# Sheet1.net
KiCad netlist of a schematic drawn in Altium Designer
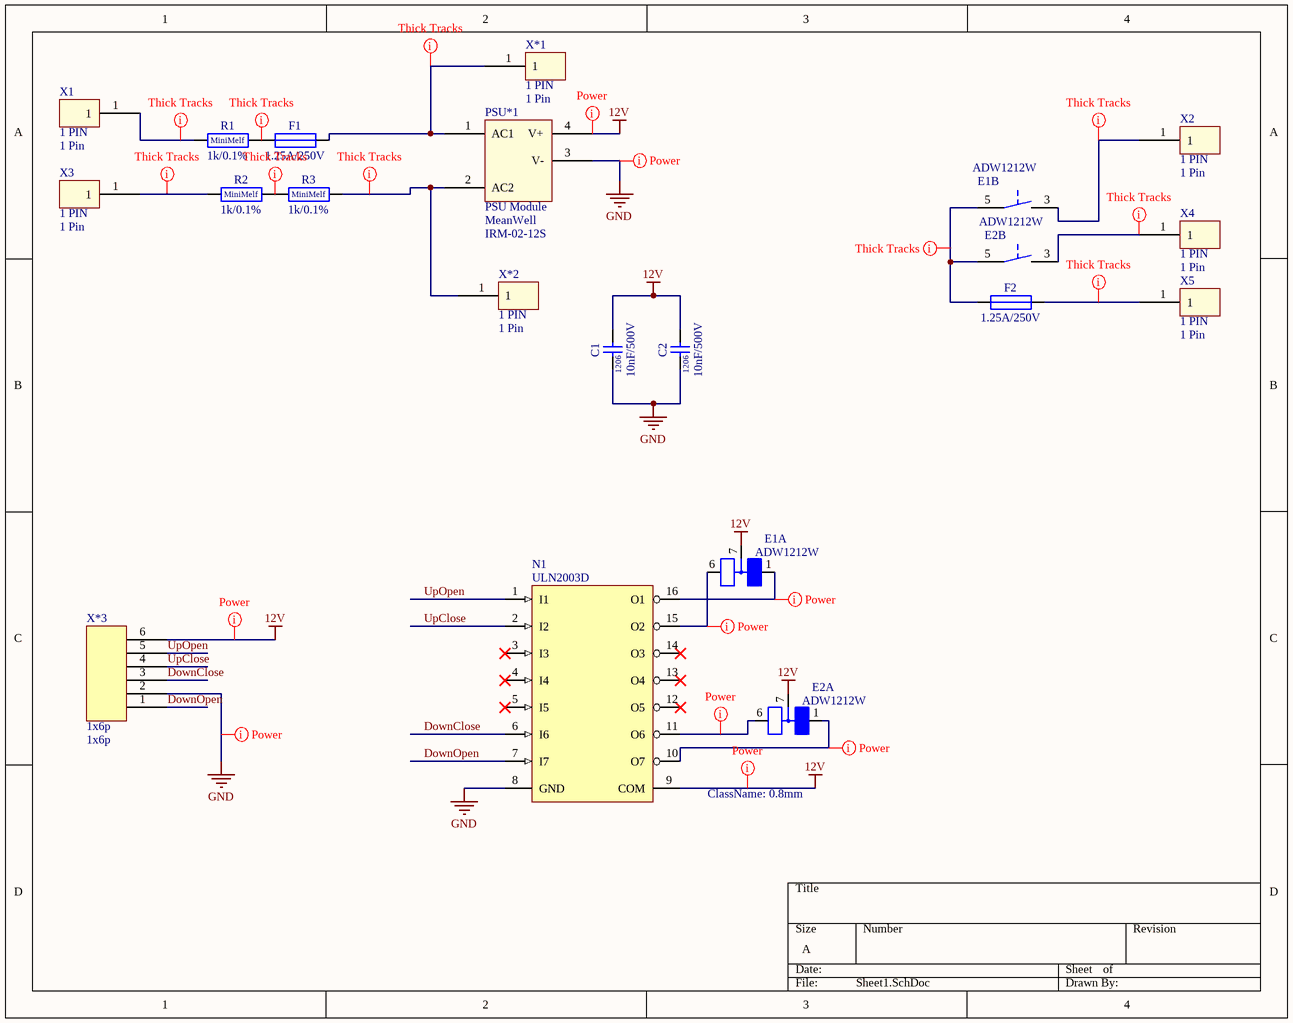
[diagram p0: Sheet1.SchDoc]

(export (version "E")
  (design (tool "Eeschema 10.0.6"))
  (components
    (comp (ref "C1")
      (value "10nF/500V")
      (footprint "CAP_1206_IPC_B")
      (description "02-1257 - SMD Capacitor 1206 10nF 500V X7R")
      (fields (field (name "PARTNUMBER") "02-1257") (field (name "PUBLISHER") "SS"))
      (libsource (lib "02_KONDENSATOREN") (part "10nF_500V_1206_02-1257"))
    )
    (comp (ref "C2")
      (value "10nF/500V")
      (footprint "CAP_1206_IPC_B")
      (description "02-1257 - SMD Capacitor 1206 10nF 500V X7R")
      (fields (field (name "PARTNUMBER") "02-1257") (field (name "PUBLISHER") "SS"))
      (libsource (lib "02_KONDENSATOREN") (part "10nF_500V_1206_02-1257"))
    )
    (comp (ref "E1")
      (value "ADW1212W")
      (footprint "RELAIS_PANASONIC_ADW1212W")
      (description "04-3960 - Relais, 12V, 1S 2Coils")
      (fields (field (name "PARTNUMBER") "04-3960") (field (name "PUBLISHER") "SS"))
      (libsource (lib "") (part "ADW1212W_04-3960_2"))
    )
    (comp (ref "E2")
      (value "ADW1212W")
      (footprint "RELAIS_PANASONIC_ADW1212W")
      (description "04-3960 - Relais, 12V, 1S 2Coils")
      (fields (field (name "PARTNUMBER") "04-3960") (field (name "PUBLISHER") "SS"))
      (libsource (lib "") (part "ADW1212W_04-3960_1"))
    )
    (comp (ref "F1")
      (value "1.25A/250V")
      (footprint "Fuse")
      (description "04-3586 - Fuse 1.25A 250V THT 8.4x4mm RM5.08mm")
      (fields (field (name "PARTNUMBER") "04-3586") (field (name "PUBLISHER") "SS"))
      (libsource (lib "AM540_rf1_1v4") (part "Fuse_1.25A_250V_04-3586"))
    )
    (comp (ref "F2")
      (value "1.25A/250V")
      (footprint "Fuse")
      (description "04-3586 - Fuse 1.25A 250V THT 8.4x4mm RM5.08mm")
      (fields (field (name "PARTNUMBER") "04-3586") (field (name "PUBLISHER") "SS"))
      (libsource (lib "AM540_rf1_1v4") (part "Fuse_1.25A_250V_04-3586"))
    )
    (comp (ref "N1")
      (value "ULN2003D")
      (footprint "SOP127P720X175-16N")
      (description "11-0373- High-Voltage, High-Current Darlington Transistor Arrays, SOP16")
      (fields (field (name "PARTNUMBER") "11-0373") (field (name "PUBLISHER") "SS"))
      (libsource (lib "Mainboard_abc082rn1_Rev18") (part "ULN2003D_11-0373"))
    )
    (comp (ref "PSU*1")
      (value "PSU Module")
      (footprint "RAC02-GB")
      (description "SMPS PCB Mode")
      (fields (field (name "MANUFACTURER") "MeanWell") (field (name "MANUFACTURER CODE") "IRM-02-12S"))
      (libsource (lib "Blinds") (part "PSU Module"))
    )
    (comp (ref "R1")
      (value "1k/0.1%")
      (footprint "RES_MiniMELF_3514N")
      (description "01-3006 - SMD Resistor MiniMelf 0.25W 0.1%")
      (fields
        (field (name "PARTNUMBER") "01-3006")
        (field (name "HELPURL") "N:\\data\\Solutions\\etw\\Projekte\\Bibliotheken\\Bauteil-Neuanlagen\\Datenblätter\\01er-Parts\\")
        (field (name "PUBLISHER") "DD")
      )
      (libsource (lib "01_WIDERSTAENDE") (part "1k_MiniMelf_01-3006"))
    )
    (comp (ref "R2")
      (value "1k/0.1%")
      (footprint "RES_MiniMELF_3514N")
      (description "01-3006 - SMD Resistor MiniMelf 0.25W 0.1%")
      (fields
        (field (name "PARTNUMBER") "01-3006")
        (field (name "HELPURL") "N:\\data\\Solutions\\etw\\Projekte\\Bibliotheken\\Bauteil-Neuanlagen\\Datenblätter\\01er-Parts\\")
        (field (name "PUBLISHER") "DD")
      )
      (libsource (lib "01_WIDERSTAENDE") (part "1k_MiniMelf_01-3006"))
    )
    (comp (ref "R3")
      (value "1k/0.1%")
      (footprint "RES_MiniMELF_3514N")
      (description "01-3006 - SMD Resistor MiniMelf 0.25W 0.1%")
      (fields
        (field (name "PARTNUMBER") "01-3006")
        (field (name "HELPURL") "N:\\data\\Solutions\\etw\\Projekte\\Bibliotheken\\Bauteil-Neuanlagen\\Datenblätter\\01er-Parts\\")
        (field (name "PUBLISHER") "DD")
      )
      (libsource (lib "01_WIDERSTAENDE") (part "1k_MiniMelf_01-3006"))
    )
    (comp (ref "X*1")
      (value "1 PIN")
      (footprint "1p")
      (fields (field (name "1") "1 Pin"))
      (libsource (lib "Blinds") (part "1 PIN"))
    )
    (comp (ref "X*2")
      (value "1 PIN")
      (footprint "1p")
      (fields (field (name "1") "1 Pin"))
      (libsource (lib "Blinds") (part "1 PIN"))
    )
    (comp (ref "X*3")
      (value "1x6p")
      (footprint "M22-5330605")
      (fields (field (name "MANUFACTURER") "TI") (field (name "MANUFACTURER CODE") "1x6p"))
      (libsource (lib "Blinds") (part "1x6p"))
    )
    (comp (ref "X1")
      (value "1 PIN")
      (footprint "1p")
      (fields (field (name "1") "1 Pin"))
      (libsource (lib "") (part "1 PIN_1"))
    )
    (comp (ref "X2")
      (value "1 PIN")
      (footprint "1p")
      (fields (field (name "1") "1 Pin"))
      (libsource (lib "Blinds") (part "1 PIN"))
    )
    (comp (ref "X3")
      (value "1 PIN")
      (footprint "1p")
      (fields (field (name "1") "1 Pin"))
      (libsource (lib "") (part "1 PIN_1"))
    )
    (comp (ref "X4")
      (value "1 PIN")
      (footprint "1p")
      (fields (field (name "1") "1 Pin"))
      (libsource (lib "Blinds") (part "1 PIN"))
    )
    (comp (ref "X5")
      (value "1 PIN")
      (footprint "1p")
      (fields (field (name "1") "1 Pin"))
      (libsource (lib "Blinds") (part "1 PIN"))
    )
  )
  (nets
    (net (code "1") (name "/DownClose") (class "Default")
      (node (ref "N1") (pin "6") (pinfunction "I6_6") (pintype "input"))
      (node (ref "X*3") (pin "3") (pintype "passive"))
    )
    (net (code "2") (name "/DownOpen") (class "Default")
      (node (ref "N1") (pin "7") (pinfunction "I7_7") (pintype "input"))
      (node (ref "X*3") (pin "1") (pintype "passive"))
    )
    (net (code "3") (name "/UpClose") (class "Default")
      (node (ref "N1") (pin "2") (pinfunction "I2_2") (pintype "input"))
      (node (ref "X*3") (pin "4") (pintype "passive"))
    )
    (net (code "4") (name "/UpOpen") (class "Default")
      (node (ref "N1") (pin "1") (pinfunction "I1_1") (pintype "input"))
      (node (ref "X*3") (pin "5") (pintype "passive"))
    )
    (net (code "5") (name "12V") (class "Default")
      (node (ref "C1") (pin "2") (pinfunction "2_2") (pintype "passive"))
      (node (ref "C2") (pin "2") (pinfunction "2_2") (pintype "passive"))
      (node (ref "E1") (pin "7") (pinfunction "P_7") (pintype "passive"))
      (node (ref "E2") (pin "7") (pinfunction "P_7") (pintype "passive"))
      (node (ref "N1") (pin "9") (pinfunction "COM_9") (pintype "passive"))
      (node (ref "PSU*1") (pin "4") (pinfunction "V+_4") (pintype "passive"))
      (node (ref "X*3") (pin "6") (pintype "passive"))
    )
    (net (code "6") (name "GND") (class "Default")
      (node (ref "C1") (pin "1") (pinfunction "1_1") (pintype "passive"))
      (node (ref "C2") (pin "1") (pinfunction "1_1") (pintype "passive"))
      (node (ref "N1") (pin "8") (pinfunction "GND_8") (pintype "power_in"))
      (node (ref "PSU*1") (pin "3") (pinfunction "V-_3") (pintype "passive"))
      (node (ref "X*3") (pin "2") (pintype "passive"))
    )
    (net (code "7") (name "Net-(E1-Pad3)") (class "Default")
      (node (ref "E1") (pin "3") (pinfunction "3_3") (pintype "passive"))
      (node (ref "X2") (pin "1") (pinfunction "1_1") (pintype "passive"))
    )
    (net (code "8") (name "Net-(E1-Pad5)") (class "Default")
      (node (ref "E1") (pin "5") (pinfunction "5_5") (pintype "passive"))
      (node (ref "E2") (pin "5") (pinfunction "5_5") (pintype "passive"))
      (node (ref "F2") (pin "1") (pinfunction "1_1") (pintype "passive"))
    )
    (net (code "9") (name "Net-(E1A-M)") (class "Default")
      (node (ref "E1") (pin "1") (pinfunction "M_1") (pintype "passive"))
      (node (ref "N1") (pin "16") (pinfunction "O1_16") (pintype "passive"))
    )
    (net (code "10") (name "Net-(E1A-M1)") (class "Default")
      (node (ref "E1") (pin "6") (pinfunction "M1_6") (pintype "passive"))
      (node (ref "N1") (pin "15") (pinfunction "O2_15") (pintype "passive"))
    )
    (net (code "11") (name "Net-(E2-Pad3)") (class "Default")
      (node (ref "E2") (pin "3") (pinfunction "3_3") (pintype "passive"))
      (node (ref "X4") (pin "1") (pinfunction "1_1") (pintype "passive"))
    )
    (net (code "12") (name "Net-(E2A-M)") (class "Default")
      (node (ref "E2") (pin "1") (pinfunction "M_1") (pintype "passive"))
      (node (ref "N1") (pin "10") (pinfunction "O7_10") (pintype "passive"))
    )
    (net (code "13") (name "Net-(E2A-M1)") (class "Default")
      (node (ref "E2") (pin "6") (pinfunction "M1_6") (pintype "passive"))
      (node (ref "N1") (pin "11") (pinfunction "O6_11") (pintype "passive"))
    )
    (net (code "14") (name "Net-(F1-Pad1)") (class "Default")
      (node (ref "F1") (pin "1") (pinfunction "1_1") (pintype "passive"))
      (node (ref "R1") (pin "2") (pinfunction "2_2") (pintype "passive"))
    )
    (net (code "15") (name "Net-(F2-Pad2)") (class "Default")
      (node (ref "F2") (pin "2") (pinfunction "2_2") (pintype "passive"))
      (node (ref "X5") (pin "1") (pinfunction "1_1") (pintype "passive"))
    )
    (net (code "16") (name "Net-(PSU*1-AC1)") (class "Default")
      (node (ref "F1") (pin "2") (pinfunction "2_2") (pintype "passive"))
      (node (ref "PSU*1") (pin "1") (pinfunction "AC1_1") (pintype "passive"))
      (node (ref "X*1") (pin "1") (pinfunction "1_1") (pintype "passive"))
    )
    (net (code "17") (name "Net-(PSU*1-AC2)") (class "Default")
      (node (ref "PSU*1") (pin "2") (pinfunction "AC2_2") (pintype "passive"))
      (node (ref "R3") (pin "2") (pinfunction "2_2") (pintype "passive"))
      (node (ref "X*2") (pin "1") (pinfunction "1_1") (pintype "passive"))
    )
    (net (code "18") (name "Net-(R1-Pad1)") (class "Default")
      (node (ref "R1") (pin "1") (pinfunction "1_1") (pintype "passive"))
      (node (ref "X1") (pin "1") (pinfunction "1_1") (pintype "passive"))
    )
    (net (code "19") (name "Net-(R2-Pad1)") (class "Default")
      (node (ref "R2") (pin "1") (pinfunction "1_1") (pintype "passive"))
      (node (ref "X3") (pin "1") (pinfunction "1_1") (pintype "passive"))
    )
    (net (code "20") (name "Net-(R2-Pad2)") (class "Default")
      (node (ref "R2") (pin "2") (pinfunction "2_2") (pintype "passive"))
      (node (ref "R3") (pin "1") (pinfunction "1_1") (pintype "passive"))
    )
    (net (code "21") (name "unconnected-(N1-I3-Pad3)") (class "Default")
      (node (ref "N1") (pin "3") (pinfunction "I3_3") (pintype "input+no_connect"))
    )
    (net (code "22") (name "unconnected-(N1-I4-Pad4)") (class "Default")
      (node (ref "N1") (pin "4") (pinfunction "I4_4") (pintype "input+no_connect"))
    )
    (net (code "23") (name "unconnected-(N1-I5-Pad5)") (class "Default")
      (node (ref "N1") (pin "5") (pinfunction "I5_5") (pintype "input+no_connect"))
    )
    (net (code "24") (name "unconnected-(N1-O3-Pad14)") (class "Default")
      (node (ref "N1") (pin "14") (pinfunction "O3_14") (pintype "passive+no_connect"))
    )
    (net (code "25") (name "unconnected-(N1-O4-Pad13)") (class "Default")
      (node (ref "N1") (pin "13") (pinfunction "O4_13") (pintype "passive+no_connect"))
    )
    (net (code "26") (name "unconnected-(N1-O5-Pad12)") (class "Default")
      (node (ref "N1") (pin "12") (pinfunction "O5_12") (pintype "passive+no_connect"))
    )
  )
)
